# Sheet1.net
KiCad netlist of a schematic drawn in Altium Designer
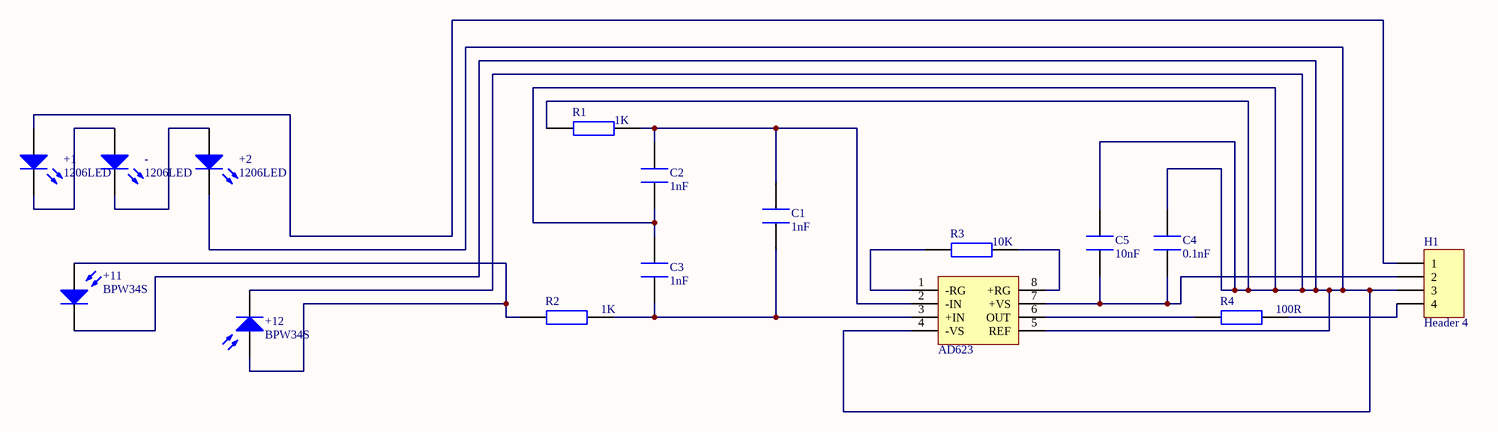
[diagram p0: Sheet1.SchDoc]

(export (version "E")
  (design (tool "Eeschema 10.0.6"))
  (components
    (comp (ref "+1")
      (value "1206LED")
      (footprint "3.2X1.6X1.1")
      (description "Typical INFRARED GaAs LED")
      (fields (field (name "PUBLISHER") "Altium Limited"))
      (libsource (lib "Miscellaneous Devices") (part "LED0"))
    )
    (comp (ref "+2")
      (value "1206LED")
      (footprint "3.2X1.6X1.1")
      (description "Typical INFRARED GaAs LED")
      (fields (field (name "PUBLISHER") "Altium Limited"))
      (libsource (lib "Miscellaneous Devices") (part "LED0"))
    )
    (comp (ref "+11")
      (value "BPW34S")
      (footprint "BPW34S")
      (description "Photosensitive Diode")
      (fields (field (name "PUBLISHER") "Altium Limited"))
      (libsource (lib "Miscellaneous Devices") (part "Photo Sen"))
    )
    (comp (ref "+12")
      (value "BPW34S")
      (footprint "BPW34S")
      (description "Photosensitive Diode")
      (fields (field (name "PUBLISHER") "Altium Limited"))
      (libsource (lib "Miscellaneous Devices") (part "Photo Sen"))
    )
    (comp (ref "-")
      (value "1206LED")
      (footprint "3.2X1.6X1.1")
      (description "Typical INFRARED GaAs LED")
      (fields (field (name "PUBLISHER") "Altium Limited"))
      (libsource (lib "Miscellaneous Devices") (part "LED0"))
    )
    (comp (ref "C1")
      (value "1nF")
      (footprint "0402")
      (description "电容")
      (libsource (lib "Schlib1") (part "CAP"))
    )
    (comp (ref "C2")
      (value "1nF")
      (footprint "0402")
      (description "电容")
      (libsource (lib "Schlib1") (part "CAP"))
    )
    (comp (ref "C3")
      (value "1nF")
      (footprint "0402")
      (description "电容")
      (libsource (lib "Schlib1") (part "CAP"))
    )
    (comp (ref "C4")
      (value "0.1nF")
      (footprint "0402")
      (description "电容")
      (libsource (lib "Schlib1") (part "CAP"))
    )
    (comp (ref "C5")
      (value "10nF")
      (footprint "0402")
      (description "电容")
      (libsource (lib "Schlib1") (part "CAP"))
    )
    (comp (ref "H1")
      (value "Header 4")
      (footprint "HDR1X4")
      (description "Header, 4-Pin")
      (fields (field (name "PUBLISHER") "Altium Limited"))
      (libsource (lib "Miscellaneous Connectors") (part "Header 4"))
    )
    (comp (ref "R1")
      (value "1K")
      (footprint "0402-A")
      (description "电阻")
      (libsource (lib "Schlib1") (part "RES"))
    )
    (comp (ref "R2")
      (value "1K")
      (footprint "0402-A")
      (description "电阻")
      (libsource (lib "Schlib1") (part "RES"))
    )
    (comp (ref "R3")
      (value "10K")
      (footprint "0402-A")
      (description "电阻")
      (libsource (lib "Schlib1") (part "RES"))
    )
    (comp (ref "R4")
      (value "100R")
      (footprint "0402-A")
      (description "电阻")
      (libsource (lib "Schlib1") (part "RES"))
    )
    (comp (ref "U1")
      (value "AD623")
      (footprint "SO8_M")
      (description "IC")
      (libsource (lib "Schlib1") (part "AD623"))
    )
  )
  (nets
    (net (code "2") (name "Net-(+1-A)") (class "Default")
      (node (ref "+1") (pin "1") (pinfunction "A_1") (pintype "passive"))
      (node (ref "H1") (pin "1") (pinfunction "1_1") (pintype "passive"))
    )
    (net (code "3") (name "Net-(+1-K)") (class "Default")
      (node (ref "+1") (pin "2") (pinfunction "K_2") (pintype "passive"))
      (node (ref "-") (pin "1") (pinfunction "A_1") (pintype "passive"))
    )
    (net (code "4") (name "Net-(+2-A)") (class "Default")
      (node (ref "+2") (pin "1") (pinfunction "A_1") (pintype "passive"))
      (node (ref "-") (pin "2") (pinfunction "K_2") (pintype "passive"))
    )
    (net (code "5") (name "Net-(+11-A)") (class "Default")
      (node (ref "+11") (pin "1") (pinfunction "A_1") (pintype "passive"))
      (node (ref "+12") (pin "1") (pinfunction "A_1") (pintype "passive"))
      (node (ref "R2") (pin "1") (pinfunction "1_1") (pintype "passive"))
    )
    (net (code "6") (name "Net-(+11-K)") (class "Default")
      (node (ref "+11") (pin "2") (pinfunction "K_2") (pintype "passive"))
      (node (ref "+12") (pin "2") (pinfunction "K_2") (pintype "passive"))
      (node (ref "+2") (pin "2") (pinfunction "K_2") (pintype "passive"))
      (node (ref "C2") (pin "1") (pinfunction "1_1") (pintype "passive"))
      (node (ref "C3") (pin "2") (pinfunction "2_2") (pintype "passive"))
      (node (ref "C4") (pin "2") (pinfunction "2_2") (pintype "passive"))
      (node (ref "C5") (pin "2") (pinfunction "2_2") (pintype "passive"))
      (node (ref "H1") (pin "3") (pinfunction "3_3") (pintype "passive"))
      (node (ref "R1") (pin "1") (pinfunction "1_1") (pintype "passive"))
      (node (ref "U1") (pin "4") (pinfunction "-VS_4") (pintype "passive"))
      (node (ref "U1") (pin "5") (pinfunction "REF_5") (pintype "passive"))
    )
    (net (code "7") (name "Net-(H1-Pad4)") (class "Default")
      (node (ref "H1") (pin "4") (pinfunction "4_4") (pintype "passive"))
      (node (ref "R4") (pin "2") (pinfunction "2_2") (pintype "passive"))
    )
    (net (code "8") (name "Net-(U1-+IN)") (class "Default")
      (node (ref "C1") (pin "1") (pinfunction "1_1") (pintype "passive"))
      (node (ref "C3") (pin "1") (pinfunction "1_1") (pintype "passive"))
      (node (ref "R2") (pin "2") (pinfunction "2_2") (pintype "passive"))
      (node (ref "U1") (pin "3") (pinfunction "+IN_3") (pintype "passive"))
    )
    (net (code "9") (name "Net-(U1-+RG)") (class "Default")
      (node (ref "R3") (pin "2") (pinfunction "2_2") (pintype "passive"))
      (node (ref "U1") (pin "8") (pinfunction "+RG_8") (pintype "passive"))
    )
    (net (code "10") (name "Net-(U1-+VS)") (class "Default")
      (node (ref "C4") (pin "1") (pinfunction "1_1") (pintype "passive"))
      (node (ref "C5") (pin "1") (pinfunction "1_1") (pintype "passive"))
      (node (ref "H1") (pin "2") (pinfunction "2_2") (pintype "passive"))
      (node (ref "U1") (pin "7") (pinfunction "+VS_7") (pintype "passive"))
    )
    (net (code "11") (name "Net-(U1--IN)") (class "Default")
      (node (ref "C1") (pin "2") (pinfunction "2_2") (pintype "passive"))
      (node (ref "C2") (pin "2") (pinfunction "2_2") (pintype "passive"))
      (node (ref "R1") (pin "2") (pinfunction "2_2") (pintype "passive"))
      (node (ref "U1") (pin "2") (pinfunction "-IN_2") (pintype "passive"))
    )
    (net (code "12") (name "Net-(U1--RG)") (class "Default")
      (node (ref "R3") (pin "1") (pinfunction "1_1") (pintype "passive"))
      (node (ref "U1") (pin "1") (pinfunction "-RG_1") (pintype "passive"))
    )
    (net (code "13") (name "Net-(U1-OUT)") (class "Default")
      (node (ref "R4") (pin "1") (pinfunction "1_1") (pintype "passive"))
      (node (ref "U1") (pin "6") (pinfunction "OUT_6") (pintype "passive"))
    )
  )
)
